# nearsens-schematic-source-2026-05-26-v1_.net
KiCad netlist of a schematic drawn in EasyEDA
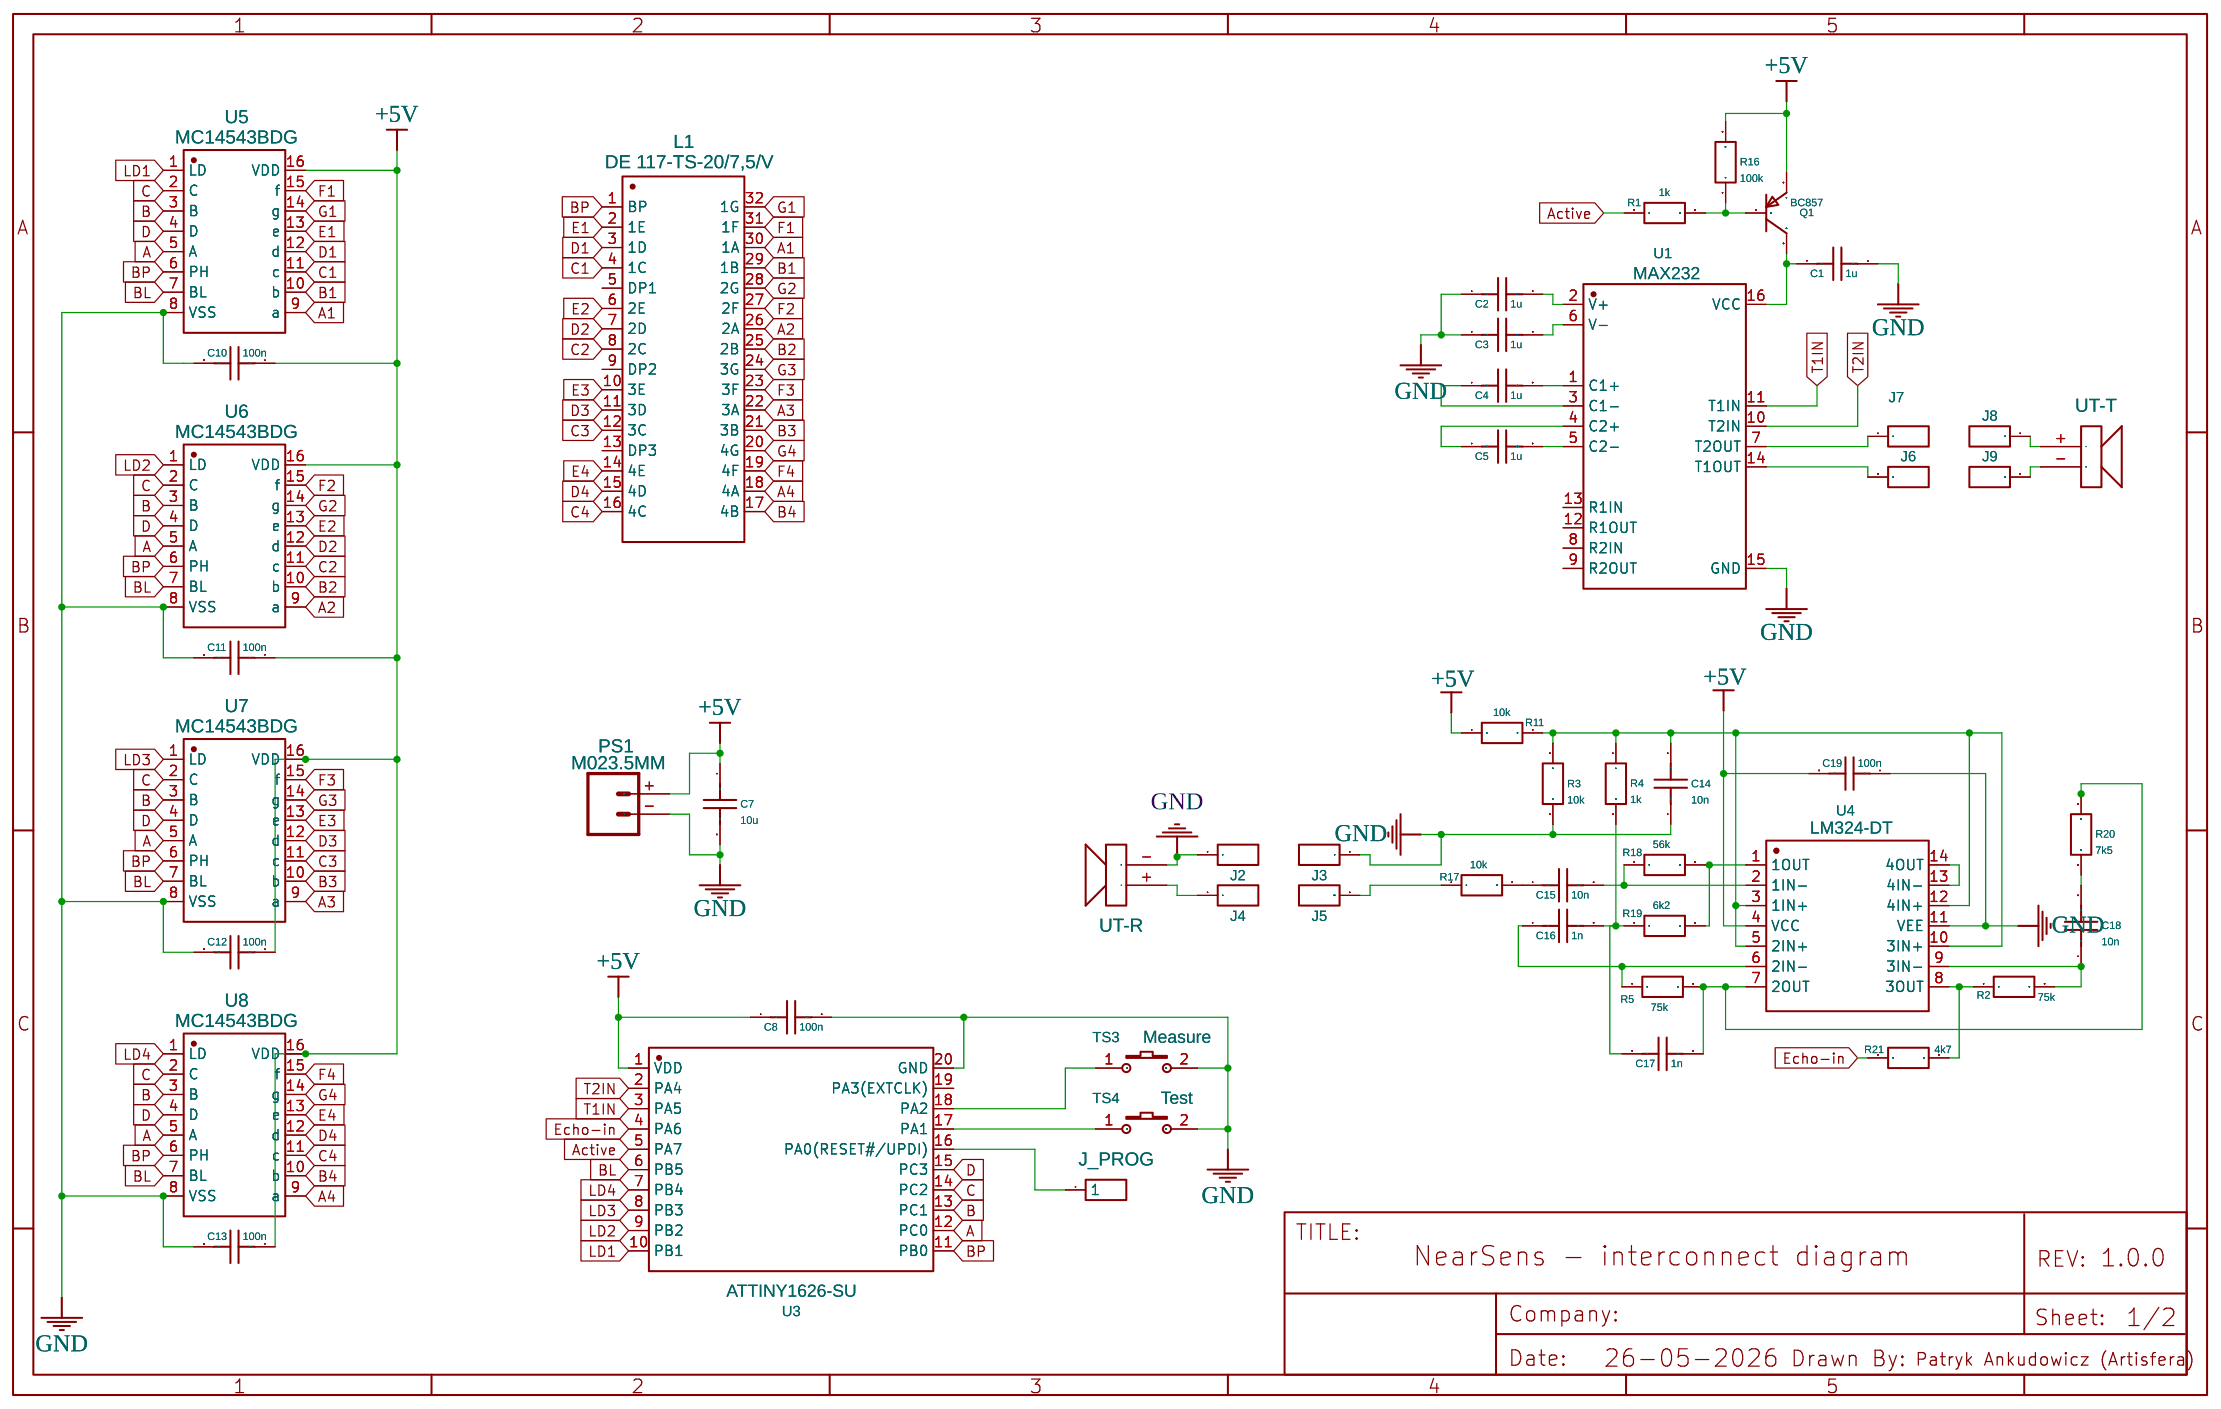
[diagram p0: schematic sheet]

(export (version "E")
  (design (tool "Eeschema 10.0.6"))
  (components
    (comp (ref "C1") (value "1u") (libsource (lib "") (part "C_0603_US_1")))
    (comp (ref "C2") (value "1u") (libsource (lib "") (part "C_0603_US_1")))
    (comp (ref "C3") (value "1u") (libsource (lib "") (part "C_0603_US_1")))
    (comp (ref "C4") (value "1u") (libsource (lib "") (part "C_0603_US_1")))
    (comp (ref "C5") (value "1u") (libsource (lib "") (part "C_0603_US_1")))
    (comp (ref "C7") (value "10u") (libsource (lib "") (part "C_0603_US_3")))
    (comp (ref "C8") (value "100n") (libsource (lib "") (part "C_0603_US_1")))
    (comp (ref "C10") (value "100n") (libsource (lib "") (part "C_0603_US_2")))
    (comp (ref "C11") (value "100n") (libsource (lib "") (part "C_0603_US_2")))
    (comp (ref "C12") (value "100n") (libsource (lib "") (part "C_0603_US_2")))
    (comp (ref "C13") (value "100n") (libsource (lib "") (part "C_0603_US_2")))
    (comp (ref "C14") (value "10n") (libsource (lib "") (part "C_0603_US")))
    (comp (ref "C15") (value "10n") (libsource (lib "") (part "C_0603_US_1")))
    (comp (ref "C16") (value "1n") (libsource (lib "") (part "C_0603_US_1")))
    (comp (ref "C17") (value "1n") (libsource (lib "") (part "C_0603_US_1")))
    (comp (ref "C18") (value "10n") (libsource (lib "") (part "C_0603_US")))
    (comp (ref "C19") (value "100n") (libsource (lib "") (part "C_0603_US_2")))
    (comp (ref "J2") (value "HDR-M-2.54_1x1") (libsource (lib "") (part "HDR-M-2.54_1x1")))
    (comp (ref "J3") (value "HDR-M-2.54_1x1") (libsource (lib "") (part "HDR-M-2.54_1x1_1")))
    (comp (ref "J4") (value "HDR-M-2.54_1x1") (libsource (lib "") (part "HDR-M-2.54_1x1")))
    (comp (ref "J5") (value "HDR-M-2.54_1x1") (libsource (lib "") (part "HDR-M-2.54_1x1_2")))
    (comp (ref "J6") (value "HDR-M-2.54_1x1") (libsource (lib "") (part "HDR-M-2.54_1x1")))
    (comp (ref "J7") (value "HDR-M-2.54_1x1") (libsource (lib "") (part "HDR-M-2.54_1x1")))
    (comp (ref "J8") (value "HDR-M-2.54_1x1") (libsource (lib "") (part "HDR-M-2.54_1x1_1")))
    (comp (ref "J9") (value "HDR-M-2.54_1x1") (libsource (lib "") (part "HDR-M-2.54_1x1_1")))
    (comp (ref "J_PROG") (value "Programming") (libsource (lib "") (part "HDR-M-2.54_1x1_3")))
    (comp (ref "L1")
      (value "DE 117-TS-20/7,5/V")
      (fields (field (name "Manufacturer") "DISPLAY ELEKTRONIK"))
      (libsource (lib "") (part "DE 117-TS-20/7,5/V DISPLAY ELEKTRONIK - Display LCD"))
    )
    (comp (ref "PS1") (value "M023.5MM") (libsource (lib "") (part "M023.5MM")))
    (comp (ref "Q1")
      (value "BC857")
      (fields
        (field (name "Manufacturer Part") "BC557(RANGE:420-800)")
        (field (name "Manufacturer") "CJ(江苏长电/长晶)")
      )
      (libsource (lib "") (part "BC557"))
    )
    (comp (ref "R1") (value "1k") (libsource (lib "") (part "R_0603_EU")))
    (comp (ref "R2") (value "75k") (libsource (lib "") (part "R_0603_EU")))
    (comp (ref "R3") (value "10k") (libsource (lib "") (part "R_0603_EU_1")))
    (comp (ref "R4") (value "1k") (libsource (lib "") (part "R_0603_EU_2")))
    (comp (ref "R5") (value "75k") (libsource (lib "") (part "R_0603_EU")))
    (comp (ref "R11") (value "10k") (libsource (lib "") (part "R_0603_EU")))
    (comp (ref "R16") (value "100k") (libsource (lib "") (part "R_0603_EU_1")))
    (comp (ref "R17") (value "10k") (libsource (lib "") (part "R_0603_EU")))
    (comp (ref "R18") (value "56k") (libsource (lib "") (part "R_0603_EU")))
    (comp (ref "R19") (value "6k2") (libsource (lib "") (part "R_0603_EU")))
    (comp (ref "R20") (value "7k5") (libsource (lib "") (part "R_0603_EU_1")))
    (comp (ref "R21") (value "4k7") (libsource (lib "") (part "R_0603_EU")))
    (comp (ref "TS3")
      (value "Measure")
      (fields (field (name "Manufacturer Part") "K2-1107ST-A4SW-06"))
      (libsource (lib "") (part "K2-3.6×6.1_SMD"))
    )
    (comp (ref "TS4")
      (value "Test")
      (fields (field (name "Manufacturer Part") "K2-1107ST-A4SW-06"))
      (libsource (lib "") (part "K2-3.6×6.1_SMD"))
    )
    (comp (ref "U1")
      (value "MAX232")
      (fields (field (name "Manufacturer Part") "MAX232ESE-EV") (field (name "Manufacturer") "EVVO(翊欧)"))
      (libsource (lib "") (part "MAX232ESE-EV"))
    )
    (comp (ref "U3")
      (value "ATTINY1626-SU")
      (fields (field (name "Manufacturer") "MICROCHIP(美国微芯)"))
      (libsource (lib "") (part "ATTINY1626-SU"))
    )
    (comp (ref "U4")
      (value "LM324-DT")
      (fields (field (name "Manufacturer Part") "LM324-DW") (field (name "Manufacturer") "DOWO(东沃)"))
      (libsource (lib "") (part "LM324-DW"))
    )
    (comp (ref "U5") (value "MC14543BDG") (libsource (lib "") (part "MC14543BDG")))
    (comp (ref "U6") (value "MC14543BDG") (libsource (lib "") (part "MC14543BDG")))
    (comp (ref "U7") (value "MC14543BDG") (libsource (lib "") (part "MC14543BDG")))
    (comp (ref "U8") (value "MC14543BDG") (libsource (lib "") (part "MC14543BDG")))
    (comp (ref "UT-R")
      (value "Przetwornik ultradzwiekowy")
      (fields (field (name "Manufacturer Part") "I47123") (field (name "Manufacturer") "I47"))
      (libsource (lib "") (part "ULTRASONIC TRANSDUCER_1"))
    )
    (comp (ref "UT-T")
      (value "Przetwornik ultradzwiekowy")
      (fields (field (name "Manufacturer Part") "I47123") (field (name "Manufacturer") "I47"))
      (libsource (lib "") (part "ULTRASONIC TRANSDUCER"))
    )
  )
  (nets
    (net (code "1") (name "+5V") (class "Default")
      (node (ref "C10") (pin "1") (pinfunction "1_1") (pintype "unspecified"))
      (node (ref "C11") (pin "1") (pinfunction "1_1") (pintype "unspecified"))
      (node (ref "C12") (pin "1") (pinfunction "1_1") (pintype "unspecified"))
      (node (ref "C13") (pin "1") (pinfunction "1_1") (pintype "unspecified"))
      (node (ref "C19") (pin "2") (pinfunction "2_2") (pintype "unspecified"))
      (node (ref "C7") (pin "1") (pinfunction "1_1") (pintype "unspecified"))
      (node (ref "C8") (pin "1") (pinfunction "1_1") (pintype "unspecified"))
      (node (ref "PS1") (pin "+") (pinfunction "2_+") (pintype "bidirectional"))
      (node (ref "Q1") (pin "2") (pinfunction "E_2") (pintype "unspecified"))
      (node (ref "R11") (pin "1") (pinfunction "1_1") (pintype "unspecified"))
      (node (ref "R16") (pin "2") (pinfunction "2_2") (pintype "unspecified"))
      (node (ref "U3") (pin "1") (pinfunction "VDD_1") (pintype "unspecified"))
      (node (ref "U4") (pin "4") (pinfunction "VCC_4") (pintype "unspecified"))
      (node (ref "U5") (pin "16") (pinfunction "VDD_16") (pintype "unspecified"))
      (node (ref "U6") (pin "16") (pinfunction "VDD_16") (pintype "unspecified"))
      (node (ref "U7") (pin "16") (pinfunction "VDD_16") (pintype "unspecified"))
      (node (ref "U8") (pin "16") (pinfunction "VDD_16") (pintype "unspecified"))
    )
    (net (code "2") (name "A") (class "Default")
      (node (ref "U3") (pin "12") (pinfunction "PC0_12") (pintype "unspecified"))
      (node (ref "U5") (pin "5") (pinfunction "A_5") (pintype "unspecified"))
      (node (ref "U6") (pin "5") (pinfunction "A_5") (pintype "unspecified"))
      (node (ref "U7") (pin "5") (pinfunction "A_5") (pintype "unspecified"))
      (node (ref "U8") (pin "5") (pinfunction "A_5") (pintype "unspecified"))
    )
    (net (code "3") (name "A1") (class "Default")
      (node (ref "L1") (pin "30") (pinfunction "1A_30") (pintype "unspecified"))
      (node (ref "U5") (pin "9") (pinfunction "a_9") (pintype "unspecified"))
    )
    (net (code "4") (name "A2") (class "Default")
      (node (ref "L1") (pin "26") (pinfunction "2A_26") (pintype "unspecified"))
      (node (ref "U6") (pin "9") (pinfunction "a_9") (pintype "unspecified"))
    )
    (net (code "5") (name "A3") (class "Default")
      (node (ref "L1") (pin "22") (pinfunction "3A_22") (pintype "unspecified"))
      (node (ref "U7") (pin "9") (pinfunction "a_9") (pintype "unspecified"))
    )
    (net (code "6") (name "A4") (class "Default")
      (node (ref "L1") (pin "18") (pinfunction "4A_18") (pintype "unspecified"))
      (node (ref "U8") (pin "9") (pinfunction "a_9") (pintype "unspecified"))
    )
    (net (code "7") (name "Active") (class "Default")
      (node (ref "R1") (pin "1") (pinfunction "1_1") (pintype "unspecified"))
      (node (ref "U3") (pin "5") (pinfunction "PA7_5") (pintype "unspecified"))
    )
    (net (code "8") (name "B") (class "Default")
      (node (ref "U3") (pin "13") (pinfunction "PC1_13") (pintype "unspecified"))
      (node (ref "U5") (pin "3") (pinfunction "B_3") (pintype "unspecified"))
      (node (ref "U6") (pin "3") (pinfunction "B_3") (pintype "unspecified"))
      (node (ref "U7") (pin "3") (pinfunction "B_3") (pintype "unspecified"))
      (node (ref "U8") (pin "3") (pinfunction "B_3") (pintype "unspecified"))
    )
    (net (code "9") (name "B1") (class "Default")
      (node (ref "L1") (pin "29") (pinfunction "1B_29") (pintype "unspecified"))
      (node (ref "U5") (pin "10") (pinfunction "b_10") (pintype "unspecified"))
    )
    (net (code "10") (name "B2") (class "Default")
      (node (ref "L1") (pin "25") (pinfunction "2B_25") (pintype "unspecified"))
      (node (ref "U6") (pin "10") (pinfunction "b_10") (pintype "unspecified"))
    )
    (net (code "11") (name "B3") (class "Default")
      (node (ref "L1") (pin "21") (pinfunction "3B_21") (pintype "unspecified"))
      (node (ref "U7") (pin "10") (pinfunction "b_10") (pintype "unspecified"))
    )
    (net (code "12") (name "B4") (class "Default")
      (node (ref "L1") (pin "17") (pinfunction "4B_17") (pintype "unspecified"))
      (node (ref "U8") (pin "10") (pinfunction "b_10") (pintype "unspecified"))
    )
    (net (code "13") (name "BL") (class "Default")
      (node (ref "U3") (pin "6") (pinfunction "PB5_6") (pintype "unspecified"))
      (node (ref "U5") (pin "7") (pinfunction "BL_7") (pintype "unspecified"))
      (node (ref "U6") (pin "7") (pinfunction "BL_7") (pintype "unspecified"))
      (node (ref "U7") (pin "7") (pinfunction "BL_7") (pintype "unspecified"))
      (node (ref "U8") (pin "7") (pinfunction "BL_7") (pintype "unspecified"))
    )
    (net (code "14") (name "BP") (class "Default")
      (node (ref "L1") (pin "1") (pinfunction "BP_1") (pintype "unspecified"))
      (node (ref "U3") (pin "11") (pinfunction "PB0_11") (pintype "unspecified"))
      (node (ref "U5") (pin "6") (pinfunction "PH_6") (pintype "unspecified"))
      (node (ref "U6") (pin "6") (pinfunction "PH_6") (pintype "unspecified"))
      (node (ref "U7") (pin "6") (pinfunction "PH_6") (pintype "unspecified"))
      (node (ref "U8") (pin "6") (pinfunction "PH_6") (pintype "unspecified"))
    )
    (net (code "15") (name "C") (class "Default")
      (node (ref "U3") (pin "14") (pinfunction "PC2_14") (pintype "unspecified"))
      (node (ref "U5") (pin "2") (pinfunction "C_2") (pintype "unspecified"))
      (node (ref "U6") (pin "2") (pinfunction "C_2") (pintype "unspecified"))
      (node (ref "U7") (pin "2") (pinfunction "C_2") (pintype "unspecified"))
      (node (ref "U8") (pin "2") (pinfunction "C_2") (pintype "unspecified"))
    )
    (net (code "16") (name "C1") (class "Default")
      (node (ref "L1") (pin "4") (pinfunction "1C_4") (pintype "unspecified"))
      (node (ref "U5") (pin "11") (pinfunction "c_11") (pintype "unspecified"))
    )
    (net (code "17") (name "C2") (class "Default")
      (node (ref "L1") (pin "8") (pinfunction "2C_8") (pintype "unspecified"))
      (node (ref "U6") (pin "11") (pinfunction "c_11") (pintype "unspecified"))
    )
    (net (code "18") (name "C3") (class "Default")
      (node (ref "L1") (pin "12") (pinfunction "3C_12") (pintype "unspecified"))
      (node (ref "U7") (pin "11") (pinfunction "c_11") (pintype "unspecified"))
    )
    (net (code "19") (name "C4") (class "Default")
      (node (ref "L1") (pin "16") (pinfunction "4C_16") (pintype "unspecified"))
      (node (ref "U8") (pin "11") (pinfunction "c_11") (pintype "unspecified"))
    )
    (net (code "20") (name "D") (class "Default")
      (node (ref "U3") (pin "15") (pinfunction "PC3_15") (pintype "unspecified"))
      (node (ref "U5") (pin "4") (pinfunction "D_4") (pintype "unspecified"))
      (node (ref "U6") (pin "4") (pinfunction "D_4") (pintype "unspecified"))
      (node (ref "U7") (pin "4") (pinfunction "D_4") (pintype "unspecified"))
      (node (ref "U8") (pin "4") (pinfunction "D_4") (pintype "unspecified"))
    )
    (net (code "21") (name "D1") (class "Default")
      (node (ref "L1") (pin "3") (pinfunction "1D_3") (pintype "unspecified"))
      (node (ref "U5") (pin "12") (pinfunction "d_12") (pintype "unspecified"))
    )
    (net (code "22") (name "D2") (class "Default")
      (node (ref "L1") (pin "7") (pinfunction "2D_7") (pintype "unspecified"))
      (node (ref "U6") (pin "12") (pinfunction "d_12") (pintype "unspecified"))
    )
    (net (code "23") (name "D3") (class "Default")
      (node (ref "L1") (pin "11") (pinfunction "3D_11") (pintype "unspecified"))
      (node (ref "U7") (pin "12") (pinfunction "d_12") (pintype "unspecified"))
    )
    (net (code "24") (name "D4") (class "Default")
      (node (ref "L1") (pin "15") (pinfunction "4D_15") (pintype "unspecified"))
      (node (ref "U8") (pin "12") (pinfunction "d_12") (pintype "unspecified"))
    )
    (net (code "25") (name "E1") (class "Default")
      (node (ref "L1") (pin "2") (pinfunction "1E_2") (pintype "unspecified"))
      (node (ref "U5") (pin "13") (pinfunction "e_13") (pintype "unspecified"))
    )
    (net (code "26") (name "E2") (class "Default")
      (node (ref "L1") (pin "6") (pinfunction "2E_6") (pintype "unspecified"))
      (node (ref "U6") (pin "13") (pinfunction "e_13") (pintype "unspecified"))
    )
    (net (code "27") (name "E3") (class "Default")
      (node (ref "L1") (pin "10") (pinfunction "3E_10") (pintype "unspecified"))
      (node (ref "U7") (pin "13") (pinfunction "e_13") (pintype "unspecified"))
    )
    (net (code "28") (name "E4") (class "Default")
      (node (ref "L1") (pin "14") (pinfunction "4E_14") (pintype "unspecified"))
      (node (ref "U8") (pin "13") (pinfunction "e_13") (pintype "unspecified"))
    )
    (net (code "29") (name "Echo-in") (class "Default")
      (node (ref "R21") (pin "1") (pinfunction "1_1") (pintype "unspecified"))
      (node (ref "U3") (pin "4") (pinfunction "PA6_4") (pintype "unspecified"))
    )
    (net (code "30") (name "F1") (class "Default")
      (node (ref "L1") (pin "31") (pinfunction "1F_31") (pintype "unspecified"))
      (node (ref "U5") (pin "15") (pinfunction "f_15") (pintype "unspecified"))
    )
    (net (code "31") (name "F2") (class "Default")
      (node (ref "L1") (pin "27") (pinfunction "2F_27") (pintype "unspecified"))
      (node (ref "U6") (pin "15") (pinfunction "f_15") (pintype "unspecified"))
    )
    (net (code "32") (name "F3") (class "Default")
      (node (ref "L1") (pin "23") (pinfunction "3F_23") (pintype "unspecified"))
      (node (ref "U7") (pin "15") (pinfunction "f_15") (pintype "unspecified"))
    )
    (net (code "33") (name "F4") (class "Default")
      (node (ref "L1") (pin "19") (pinfunction "4F_19") (pintype "unspecified"))
      (node (ref "U8") (pin "15") (pinfunction "f_15") (pintype "unspecified"))
    )
    (net (code "34") (name "G1") (class "Default")
      (node (ref "L1") (pin "32") (pinfunction "1G_32") (pintype "unspecified"))
      (node (ref "U5") (pin "14") (pinfunction "g_14") (pintype "unspecified"))
    )
    (net (code "35") (name "G2") (class "Default")
      (node (ref "L1") (pin "28") (pinfunction "2G_28") (pintype "unspecified"))
      (node (ref "U6") (pin "14") (pinfunction "g_14") (pintype "unspecified"))
    )
    (net (code "36") (name "G3") (class "Default")
      (node (ref "L1") (pin "24") (pinfunction "3G_24") (pintype "unspecified"))
      (node (ref "U7") (pin "14") (pinfunction "g_14") (pintype "unspecified"))
    )
    (net (code "37") (name "G4") (class "Default")
      (node (ref "L1") (pin "20") (pinfunction "4G_20") (pintype "unspecified"))
      (node (ref "U8") (pin "14") (pinfunction "g_14") (pintype "unspecified"))
    )
    (net (code "38") (name "GND") (class "Default")
      (node (ref "C1") (pin "2") (pinfunction "2_2") (pintype "unspecified"))
      (node (ref "C10") (pin "2") (pinfunction "2_2") (pintype "unspecified"))
      (node (ref "C11") (pin "2") (pinfunction "2_2") (pintype "unspecified"))
      (node (ref "C12") (pin "2") (pinfunction "2_2") (pintype "unspecified"))
      (node (ref "C13") (pin "2") (pinfunction "2_2") (pintype "unspecified"))
      (node (ref "C14") (pin "1") (pinfunction "1_1") (pintype "unspecified"))
      (node (ref "C19") (pin "1") (pinfunction "1_1") (pintype "unspecified"))
      (node (ref "C2") (pin "1") (pinfunction "1_1") (pintype "unspecified"))
      (node (ref "C3") (pin "1") (pinfunction "1_1") (pintype "unspecified"))
      (node (ref "C7") (pin "2") (pinfunction "2_2") (pintype "unspecified"))
      (node (ref "C8") (pin "2") (pinfunction "2_2") (pintype "unspecified"))
      (node (ref "J2") (pin "1") (pinfunction "1_1") (pintype "input"))
      (node (ref "J3") (pin "1") (pinfunction "1_1") (pintype "input"))
      (node (ref "PS1") (pin "-") (pinfunction "1_-") (pintype "bidirectional"))
      (node (ref "R3") (pin "1") (pinfunction "1_1") (pintype "unspecified"))
      (node (ref "TS3") (pin "2") (pinfunction "2_2") (pintype "unspecified"))
      (node (ref "TS4") (pin "2") (pinfunction "2_2") (pintype "unspecified"))
      (node (ref "U1") (pin "15") (pinfunction "GND_15") (pintype "unspecified"))
      (node (ref "U3") (pin "20") (pinfunction "GND_20") (pintype "unspecified"))
      (node (ref "U4") (pin "11") (pinfunction "VEE_11") (pintype "unspecified"))
      (node (ref "U5") (pin "8") (pinfunction "VSS_8") (pintype "unspecified"))
      (node (ref "U6") (pin "8") (pinfunction "VSS_8") (pintype "unspecified"))
      (node (ref "U7") (pin "8") (pinfunction "VSS_8") (pintype "unspecified"))
      (node (ref "U8") (pin "8") (pinfunction "VSS_8") (pintype "unspecified"))
      (node (ref "UT-R") (pin "-") (pinfunction "+_-") (pintype "bidirectional"))
    )
    (net (code "39") (name "LD1") (class "Default")
      (node (ref "U3") (pin "10") (pinfunction "PB1_10") (pintype "unspecified"))
      (node (ref "U5") (pin "1") (pinfunction "LD_1") (pintype "unspecified"))
    )
    (net (code "40") (name "LD2") (class "Default")
      (node (ref "U3") (pin "9") (pinfunction "PB2_9") (pintype "unspecified"))
      (node (ref "U6") (pin "1") (pinfunction "LD_1") (pintype "unspecified"))
    )
    (net (code "41") (name "LD3") (class "Default")
      (node (ref "U3") (pin "8") (pinfunction "PB3_8") (pintype "unspecified"))
      (node (ref "U7") (pin "1") (pinfunction "LD_1") (pintype "unspecified"))
    )
    (net (code "42") (name "LD4") (class "Default")
      (node (ref "U3") (pin "7") (pinfunction "PB4_7") (pintype "unspecified"))
      (node (ref "U8") (pin "1") (pinfunction "LD_1") (pintype "unspecified"))
    )
    (net (code "43") (name "Net-(C15-Pad1)") (class "Default")
      (node (ref "C15") (pin "1") (pinfunction "1_1") (pintype "unspecified"))
      (node (ref "R17") (pin "2") (pinfunction "2_2") (pintype "unspecified"))
    )
    (net (code "44") (name "Net-(C16-Pad2)") (class "Default")
      (node (ref "C16") (pin "2") (pinfunction "2_2") (pintype "unspecified"))
      (node (ref "C17") (pin "1") (pinfunction "1_1") (pintype "unspecified"))
      (node (ref "R19") (pin "1") (pinfunction "1_1") (pintype "unspecified"))
      (node (ref "R4") (pin "2") (pinfunction "2_2") (pintype "unspecified"))
    )
    (net (code "45") (name "Net-(C18-Pad2)") (class "Default")
      (node (ref "C18") (pin "2") (pinfunction "2_2") (pintype "unspecified"))
      (node (ref "R20") (pin "1") (pinfunction "1_1") (pintype "unspecified"))
    )
    (net (code "46") (name "Net-(J5-PAD)") (class "Default")
      (node (ref "J5") (pin "1") (pinfunction "PAD_1") (pintype "input"))
      (node (ref "R17") (pin "1") (pinfunction "1_1") (pintype "unspecified"))
    )
    (net (code "47") (name "Net-(Q1-B)") (class "Default")
      (node (ref "Q1") (pin "1") (pinfunction "B_1") (pintype "unspecified"))
      (node (ref "R1") (pin "2") (pinfunction "2_2") (pintype "unspecified"))
      (node (ref "R16") (pin "1") (pinfunction "1_1") (pintype "unspecified"))
    )
    (net (code "48") (name "Net-(Q1-C)") (class "Default")
      (node (ref "C1") (pin "1") (pinfunction "1_1") (pintype "unspecified"))
      (node (ref "Q1") (pin "3") (pinfunction "C_3") (pintype "unspecified"))
      (node (ref "U1") (pin "16") (pinfunction "VCC_16") (pintype "unspecified"))
    )
    (net (code "49") (name "Net-(U1-C1+)") (class "Default")
      (node (ref "C4") (pin "2") (pinfunction "2_2") (pintype "unspecified"))
      (node (ref "U1") (pin "1") (pinfunction "C1+_1") (pintype "unspecified"))
    )
    (net (code "50") (name "Net-(U1-C1-)") (class "Default")
      (node (ref "C4") (pin "1") (pinfunction "1_1") (pintype "unspecified"))
      (node (ref "U1") (pin "3") (pinfunction "C1-_3") (pintype "unspecified"))
    )
    (net (code "51") (name "Net-(U1-C2+)") (class "Default")
      (node (ref "C5") (pin "1") (pinfunction "1_1") (pintype "unspecified"))
      (node (ref "U1") (pin "4") (pinfunction "C2+_4") (pintype "unspecified"))
    )
    (net (code "52") (name "Net-(U1-C2-)") (class "Default")
      (node (ref "C5") (pin "2") (pinfunction "2_2") (pintype "unspecified"))
      (node (ref "U1") (pin "5") (pinfunction "C2-_5") (pintype "unspecified"))
    )
    (net (code "53") (name "Net-(U1-T1OUT)") (class "Default")
      (node (ref "J6") (pin "1") (pinfunction "1_1") (pintype "input"))
      (node (ref "U1") (pin "14") (pinfunction "T1OUT_14") (pintype "unspecified"))
    )
    (net (code "54") (name "Net-(U1-T2OUT)") (class "Default")
      (node (ref "J7") (pin "1") (pinfunction "1_1") (pintype "input"))
      (node (ref "U1") (pin "7") (pinfunction "T2OUT_7") (pintype "unspecified"))
    )
    (net (code "55") (name "Net-(U1-V+)") (class "Default")
      (node (ref "C2") (pin "2") (pinfunction "2_2") (pintype "unspecified"))
      (node (ref "U1") (pin "2") (pinfunction "V+_2") (pintype "unspecified"))
    )
    (net (code "56") (name "Net-(U1-V-)") (class "Default")
      (node (ref "C3") (pin "2") (pinfunction "2_2") (pintype "unspecified"))
      (node (ref "U1") (pin "6") (pinfunction "V-_6") (pintype "unspecified"))
    )
    (net (code "57") (name "Net-(U3-PA0(RESET#{slash}UPDI))") (class "Default")
      (node (ref "J_PROG") (pin "1") (pinfunction "1_1") (pintype "input"))
      (node (ref "U3") (pin "16") (pinfunction "PA0(RESET#/UPDI)_16") (pintype "unspecified"))
    )
    (net (code "58") (name "Net-(U3-PA1)") (class "Default")
      (node (ref "TS4") (pin "1") (pinfunction "1_1") (pintype "unspecified"))
      (node (ref "U3") (pin "17") (pinfunction "PA1_17") (pintype "unspecified"))
    )
    (net (code "59") (name "Net-(U3-PA2)") (class "Default")
      (node (ref "TS3") (pin "1") (pinfunction "1_1") (pintype "unspecified"))
      (node (ref "U3") (pin "18") (pinfunction "PA2_18") (pintype "unspecified"))
    )
    (net (code "60") (name "Net-(U4-1IN+)") (class "Default")
      (node (ref "C14") (pin "2") (pinfunction "2_2") (pintype "unspecified"))
      (node (ref "R11") (pin "2") (pinfunction "2_2") (pintype "unspecified"))
      (node (ref "R3") (pin "2") (pinfunction "2_2") (pintype "unspecified"))
      (node (ref "R4") (pin "1") (pinfunction "1_1") (pintype "unspecified"))
      (node (ref "U4") (pin "10") (pinfunction "3IN+_10") (pintype "unspecified"))
      (node (ref "U4") (pin "12") (pinfunction "4IN+_12") (pintype "unspecified"))
      (node (ref "U4") (pin "3") (pinfunction "1IN+_3") (pintype "unspecified"))
      (node (ref "U4") (pin "5") (pinfunction "2IN+_5") (pintype "unspecified"))
    )
    (net (code "61") (name "Net-(U4-1IN-)") (class "Default")
      (node (ref "C15") (pin "2") (pinfunction "2_2") (pintype "unspecified"))
      (node (ref "R18") (pin "1") (pinfunction "1_1") (pintype "unspecified"))
      (node (ref "U4") (pin "2") (pinfunction "1IN-_2") (pintype "unspecified"))
    )
    (net (code "62") (name "Net-(U4-1OUT)") (class "Default")
      (node (ref "R18") (pin "2") (pinfunction "2_2") (pintype "unspecified"))
      (node (ref "R19") (pin "2") (pinfunction "2_2") (pintype "unspecified"))
      (node (ref "U4") (pin "1") (pinfunction "1OUT_1") (pintype "unspecified"))
    )
    (net (code "63") (name "Net-(U4-2IN-)") (class "Default")
      (node (ref "C16") (pin "1") (pinfunction "1_1") (pintype "unspecified"))
      (node (ref "R5") (pin "1") (pinfunction "1_1") (pintype "unspecified"))
      (node (ref "U4") (pin "6") (pinfunction "2IN-_6") (pintype "unspecified"))
    )
    (net (code "64") (name "Net-(U4-2OUT)") (class "Default")
      (node (ref "C17") (pin "2") (pinfunction "2_2") (pintype "unspecified"))
      (node (ref "R20") (pin "2") (pinfunction "2_2") (pintype "unspecified"))
      (node (ref "R5") (pin "2") (pinfunction "2_2") (pintype "unspecified"))
      (node (ref "U4") (pin "7") (pinfunction "2OUT_7") (pintype "unspecified"))
    )
    (net (code "65") (name "Net-(U4-3IN-)") (class "Default")
      (node (ref "C18") (pin "1") (pinfunction "1_1") (pintype "unspecified"))
      (node (ref "R2") (pin "2") (pinfunction "2_2") (pintype "unspecified"))
      (node (ref "U4") (pin "9") (pinfunction "3IN-_9") (pintype "unspecified"))
    )
    (net (code "66") (name "Net-(U4-3OUT)") (class "Default")
      (node (ref "R2") (pin "1") (pinfunction "1_1") (pintype "unspecified"))
      (node (ref "R21") (pin "2") (pinfunction "2_2") (pintype "unspecified"))
      (node (ref "U4") (pin "8") (pinfunction "3OUT_8") (pintype "unspecified"))
    )
    (net (code "67") (name "Net-(U4-4IN-)") (class "Default")
      (node (ref "U4") (pin "13") (pinfunction "4IN-_13") (pintype "unspecified"))
      (node (ref "U4") (pin "14") (pinfunction "4OUT_14") (pintype "unspecified"))
    )
    (net (code "68") (name "Net-(UT-R--)") (class "Default")
      (node (ref "J4") (pin "1") (pinfunction "1_1") (pintype "input"))
      (node (ref "UT-R") (pin "+") (pinfunction "-_+") (pintype "bidirectional"))
    )
    (net (code "69") (name "Net-(UT-T-+)") (class "Default")
      (node (ref "J9") (pin "1") (pinfunction "1_1") (pintype "input"))
      (node (ref "UT-T") (pin "-") (pinfunction "+_-") (pintype "bidirectional"))
    )
    (net (code "70") (name "Net-(UT-T--)") (class "Default")
      (node (ref "J8") (pin "1") (pinfunction "1_1") (pintype "input"))
      (node (ref "UT-T") (pin "+") (pinfunction "-_+") (pintype "bidirectional"))
    )
    (net (code "71") (name "T1IN") (class "Default")
      (node (ref "U1") (pin "11") (pinfunction "T1IN_11") (pintype "unspecified"))
      (node (ref "U3") (pin "3") (pinfunction "PA5_3") (pintype "unspecified"))
    )
    (net (code "72") (name "T2IN") (class "Default")
      (node (ref "U1") (pin "10") (pinfunction "T2IN_10") (pintype "unspecified"))
      (node (ref "U3") (pin "2") (pinfunction "PA4_2") (pintype "unspecified"))
    )
    (net (code "73") (name "unconnected-(L1-DP1-Pad5)") (class "Default")
      (node (ref "L1") (pin "5") (pinfunction "DP1_5") (pintype "unspecified"))
    )
    (net (code "74") (name "unconnected-(L1-DP2-Pad9)") (class "Default")
      (node (ref "L1") (pin "9") (pinfunction "DP2_9") (pintype "unspecified"))
    )
    (net (code "75") (name "unconnected-(L1-DP3-Pad13)") (class "Default")
      (node (ref "L1") (pin "13") (pinfunction "DP3_13") (pintype "unspecified"))
    )
    (net (code "76") (name "unconnected-(U1-R1IN-Pad13)") (class "Default")
      (node (ref "U1") (pin "13") (pinfunction "R1IN_13") (pintype "unspecified"))
    )
    (net (code "77") (name "unconnected-(U1-R1OUT-Pad12)") (class "Default")
      (node (ref "U1") (pin "12") (pinfunction "R1OUT_12") (pintype "unspecified"))
    )
    (net (code "78") (name "unconnected-(U1-R2IN-Pad8)") (class "Default")
      (node (ref "U1") (pin "8") (pinfunction "R2IN_8") (pintype "unspecified"))
    )
    (net (code "79") (name "unconnected-(U1-R2OUT-Pad9)") (class "Default")
      (node (ref "U1") (pin "9") (pinfunction "R2OUT_9") (pintype "unspecified"))
    )
    (net (code "80") (name "unconnected-(U3-PA3(EXTCLK)-Pad19)") (class "Default")
      (node (ref "U3") (pin "19") (pinfunction "PA3(EXTCLK)_19") (pintype "unspecified"))
    )
  )
)
